# ESP8266Watch-dev-Sch.net
KiCad netlist of a schematic drawn in Altium Designer
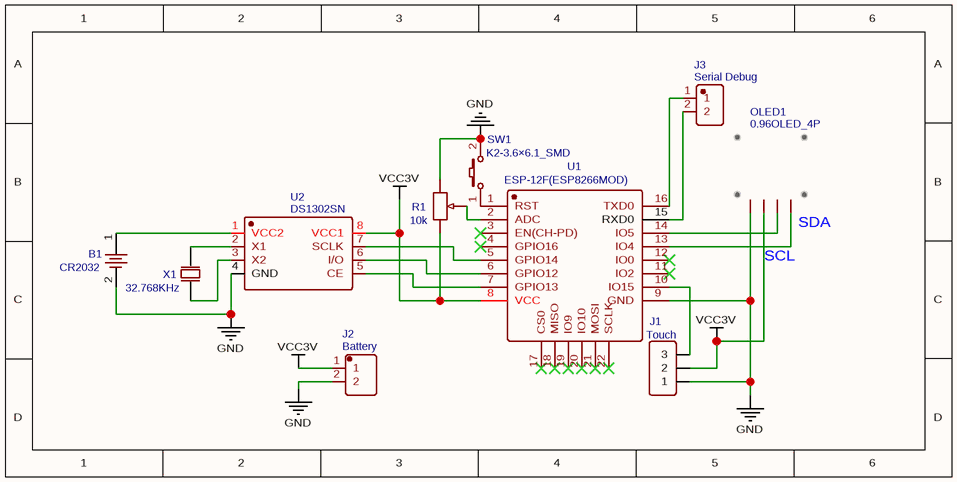
[diagram p0: ESP8266Watch-dev-Sch.schdoc]

(export (version "E")
  (design (tool "Eeschema 10.0.6"))
  (components
    (comp (ref "B1")
      (value "CR2032")
      (fields (field (name "BOM_MANUFACTURER PART") "BS-2-1") (field (name "BOM_SUPPLIER PART") "C70376"))
      (libsource (lib "altium-import") (part "root_3_CR2032_"))
    )
    (comp (ref "J1")
      (value "Touch")
      (fields
        (field (name "BOM_SUPPLIER PART") "C146243")
        (field (name "BOM_MANUFACTURER PART") "Header-Female-2.54_1x3")
      )
      (libsource (lib "altium-import") (part "root_2_Touch_"))
    )
    (comp (ref "J2")
      (value "Battery")
      (fields (field (name "BOM_SUPPLIER PART") "C2324") (field (name "BOM_MANUFACTURER PART") "1.25T-1-2A"))
      (libsource (lib "altium-import") (part "root_0_Battery_"))
    )
    (comp (ref "J3")
      (value "Serial Debug")
      (fields
        (field (name "BOM_SUPPLIER PART") "C2879963")
        (field (name "BOM_MANUFACTURER PART") "A2005WV-2P")
        (field (name "CONTRIBUTOR") "LCSC")
      )
      (libsource (lib "altium-import") (part "root_0_Serial Debug_"))
    )
    (comp (ref "OLED1")
      (value "0.96OLED_4P")
      (fields (field (name "CONTRIBUTOR") "LCEDA_Lib"))
      (libsource (lib "altium-import") (part "root_0_0.96OLED_4P_"))
    )
    (comp (ref "R1")
      (value "10k")
      (fields (field (name "CONTRIBUTOR") "LCEDA_Lib"))
      (libsource (lib "altium-import") (part "root_3_10k_"))
    )
    (comp (ref "SW1")
      (value "K2-3.6×6.1_SMD")
      (fields
        (field (name "BOM_SUPPLIER PART") "C118141")
        (field (name "BOM_MANUFACTURER PART") "K2-1107ST-A4SW-06")
        (field (name "CONTRIBUTOR") "LCEDA_Lib")
      )
      (libsource (lib "altium-import") (part "root_1_K2-3.6×6.1_SMD_"))
    )
    (comp (ref "U1")
      (value "ESP-12F(ESP8266MOD)")
      (fields (field (name "BOM_SUPPLIER PART") "C82891"))
      (libsource (lib "altium-import") (part "root_0_ESP-12F(ESP8266MOD)_"))
    )
    (comp (ref "U2")
      (value "DS1302SN")
      (fields
        (field (name "BOM_MANUFACTURER PART") "DS1302SN+T&R")
        (field (name "BOM_SUPPLIER PART") "C41719")
      )
      (libsource (lib "altium-import") (part "root_0_DS1302SN_"))
    )
    (comp (ref "X1")
      (value "32.768KHz")
      (fields
        (field (name "BOM_SUPPLIER PART") "C100098")
        (field (name "BOM_MANUFACTURER PART") "CFS-20632768DZFB")
        (field (name "CONTRIBUTOR") "LCSC")
      )
      (libsource (lib "altium-import") (part "root_1_32.768KHz_"))
    )
  )
  (nets
    (net (code "1") (name "GND") (class "Default")
      (node (ref "B1") (pin "2") (pinfunction "2_2") (pintype "passive"))
      (node (ref "J1") (pin "1") (pinfunction "1_1") (pintype "passive"))
      (node (ref "J2") (pin "2") (pinfunction "2_2") (pintype "passive"))
      (node (ref "OLED1") (pin "1") (pinfunction "1_1") (pintype "passive"))
      (node (ref "R1") (pin "1") (pinfunction "1_1") (pintype "passive"))
      (node (ref "SW1") (pin "2") (pinfunction "2_2") (pintype "passive"))
      (node (ref "U1") (pin "9") (pinfunction "GND_9") (pintype "passive"))
      (node (ref "U2") (pin "4") (pinfunction "GND_4") (pintype "passive"))
    )
    (net (code "2") (name "Net-(U1-ADC)") (class "Default")
      (node (ref "R1") (pin "2") (pinfunction "2_2") (pintype "passive"))
      (node (ref "U1") (pin "2") (pinfunction "ADC_2") (pintype "passive"))
    )
    (net (code "3") (name "Net-(U1-GPIO12)") (class "Default")
      (node (ref "U1") (pin "6") (pinfunction "GPIO12_6") (pintype "passive"))
      (node (ref "U2") (pin "6") (pinfunction "I/O_6") (pintype "passive"))
    )
    (net (code "4") (name "Net-(U1-GPIO13)") (class "Default")
      (node (ref "U1") (pin "7") (pinfunction "GPIO13_7") (pintype "passive"))
      (node (ref "U2") (pin "5") (pinfunction "CE_5") (pintype "passive"))
    )
    (net (code "5") (name "Net-(U1-GPIO14)") (class "Default")
      (node (ref "U1") (pin "5") (pinfunction "GPIO14_5") (pintype "passive"))
      (node (ref "U2") (pin "7") (pinfunction "SCLK_7") (pintype "passive"))
    )
    (net (code "6") (name "Net-(U1-IO4)") (class "Default")
      (node (ref "OLED1") (pin "4") (pinfunction "4_4") (pintype "passive"))
      (node (ref "U1") (pin "13") (pinfunction "IO4_13") (pintype "passive"))
    )
    (net (code "7") (name "Net-(U1-IO5)") (class "Default")
      (node (ref "OLED1") (pin "3") (pinfunction "3_3") (pintype "passive"))
      (node (ref "U1") (pin "14") (pinfunction "IO5_14") (pintype "passive"))
    )
    (net (code "8") (name "Net-(U1-IO15)") (class "Default")
      (node (ref "J1") (pin "3") (pinfunction "3_3") (pintype "passive"))
      (node (ref "U1") (pin "10") (pinfunction "IO15_10") (pintype "passive"))
    )
    (net (code "9") (name "Net-(U1-RST)") (class "Default")
      (node (ref "SW1") (pin "1") (pinfunction "1_1") (pintype "passive"))
      (node (ref "U1") (pin "1") (pinfunction "RST_1") (pintype "passive"))
    )
    (net (code "10") (name "Net-(U1-RXD0)") (class "Default")
      (node (ref "J3") (pin "2") (pinfunction "2_2") (pintype "passive"))
      (node (ref "U1") (pin "15") (pinfunction "RXD0_15") (pintype "passive"))
    )
    (net (code "11") (name "Net-(U1-TXD0)") (class "Default")
      (node (ref "J3") (pin "1") (pinfunction "1_1") (pintype "passive"))
      (node (ref "U1") (pin "16") (pinfunction "TXD0_16") (pintype "passive"))
    )
    (net (code "12") (name "Net-(U2-VCC2)") (class "Default")
      (node (ref "B1") (pin "1") (pinfunction "1_1") (pintype "passive"))
      (node (ref "U2") (pin "1") (pinfunction "VCC2_1") (pintype "passive"))
    )
    (net (code "13") (name "Net-(U2-X1)") (class "Default")
      (node (ref "U2") (pin "2") (pinfunction "X1_2") (pintype "passive"))
      (node (ref "X1") (pin "2") (pinfunction "OSC2_2") (pintype "passive"))
    )
    (net (code "14") (name "Net-(U2-X2)") (class "Default")
      (node (ref "U2") (pin "3") (pinfunction "X2_3") (pintype "passive"))
      (node (ref "X1") (pin "1") (pinfunction "OSC1_1") (pintype "passive"))
    )
    (net (code "15") (name "VCC3V") (class "Default")
      (node (ref "J1") (pin "2") (pinfunction "2_2") (pintype "passive"))
      (node (ref "J2") (pin "1") (pinfunction "1_1") (pintype "passive"))
      (node (ref "OLED1") (pin "2") (pinfunction "2_2") (pintype "passive"))
      (node (ref "R1") (pin "3") (pinfunction "3_3") (pintype "passive"))
      (node (ref "U1") (pin "8") (pinfunction "VCC_8") (pintype "passive"))
      (node (ref "U2") (pin "8") (pinfunction "VCC1_8") (pintype "passive"))
    )
    (net (code "16") (name "unconnected-(U1-CS0-Pad17)") (class "Default")
      (node (ref "U1") (pin "17") (pinfunction "CS0_17") (pintype "passive+no_connect"))
    )
    (net (code "17") (name "unconnected-(U1-EN(CH-PD)-Pad3)") (class "Default")
      (node (ref "U1") (pin "3") (pinfunction "EN(CH-PD)_3") (pintype "passive+no_connect"))
    )
    (net (code "18") (name "unconnected-(U1-GPIO16-Pad4)") (class "Default")
      (node (ref "U1") (pin "4") (pinfunction "GPIO16_4") (pintype "passive+no_connect"))
    )
    (net (code "19") (name "unconnected-(U1-IO0-Pad12)") (class "Default")
      (node (ref "U1") (pin "12") (pinfunction "IO0_12") (pintype "passive+no_connect"))
    )
    (net (code "20") (name "unconnected-(U1-IO2-Pad11)") (class "Default")
      (node (ref "U1") (pin "11") (pinfunction "IO2_11") (pintype "passive+no_connect"))
    )
    (net (code "21") (name "unconnected-(U1-IO9-Pad19)") (class "Default")
      (node (ref "U1") (pin "19") (pinfunction "IO9_19") (pintype "passive+no_connect"))
    )
    (net (code "22") (name "unconnected-(U1-IO10-Pad20)") (class "Default")
      (node (ref "U1") (pin "20") (pinfunction "IO10_20") (pintype "passive+no_connect"))
    )
    (net (code "23") (name "unconnected-(U1-MISO-Pad18)") (class "Default")
      (node (ref "U1") (pin "18") (pinfunction "MISO_18") (pintype "passive+no_connect"))
    )
    (net (code "24") (name "unconnected-(U1-MOSI-Pad21)") (class "Default")
      (node (ref "U1") (pin "21") (pinfunction "MOSI_21") (pintype "passive+no_connect"))
    )
    (net (code "25") (name "unconnected-(U1-SCLK-Pad22)") (class "Default")
      (node (ref "U1") (pin "22") (pinfunction "SCLK_22") (pintype "passive+no_connect"))
    )
  )
)
